# MST3K_Billboard.net
KiCad netlist of a schematic drawn in EAGLE
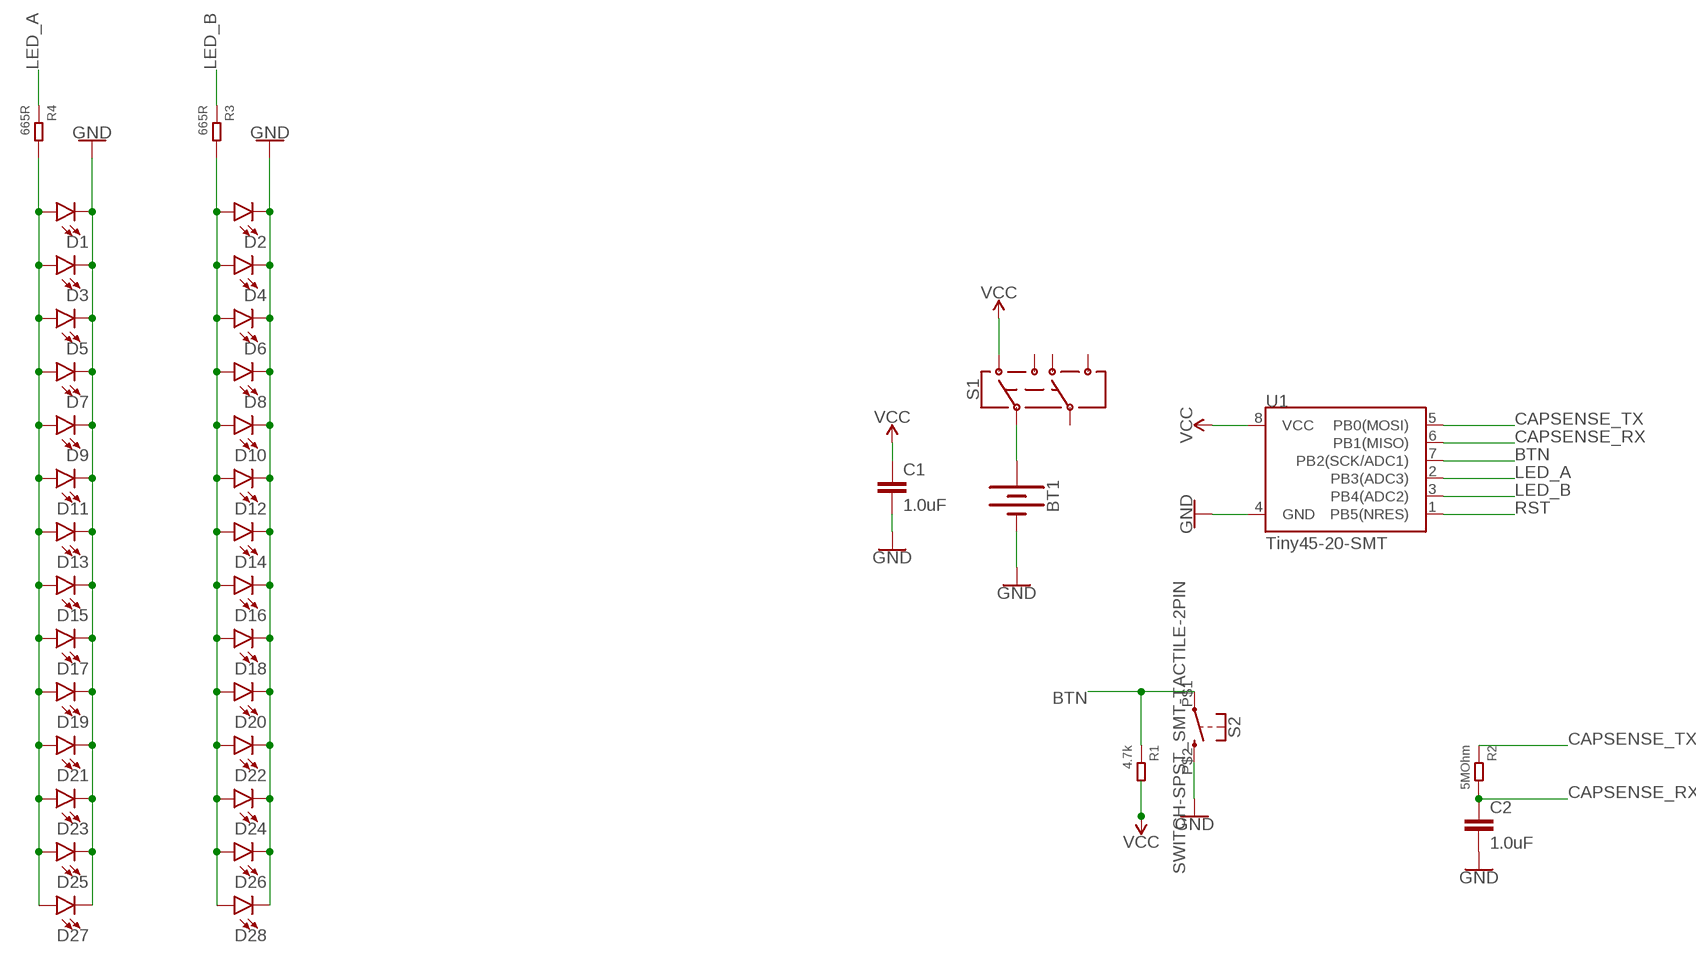
[diagram p0: schematic, sheet 1]

(export (version "E")
  (design (tool "Eeschema 10.0.6"))
  (components
    (comp (ref "BT1")
      (value "BATTERY-20MM_SMD_4LEGS")
      (footprint "eagle-import:BATTCON_20MM_4LEGS")
      (libsource (lib "eagle-import") (part "BATTERY-20MM_SMD_4LEGS"))
    )
    (comp (ref "C1")
      (value "1.0uF")
      (footprint "eagle-import:0805")
      (libsource (lib "eagle-import") (part "1.0UF-0805-25V-10%"))
    )
    (comp (ref "C2")
      (value "1.0uF")
      (footprint "eagle-import:0805")
      (libsource (lib "eagle-import") (part "1.0UF-0805-25V-10%"))
    )
    (comp (ref "D1")
      (value "LED-3MM-NO_SILK")
      (footprint "eagle-import:LED_3MM-NS")
      (libsource (lib "eagle-import") (part "LED-3MM-NO_SILK"))
    )
    (comp (ref "D2")
      (value "LED-3MM-NO_SILK")
      (footprint "eagle-import:LED_3MM-NS")
      (libsource (lib "eagle-import") (part "LED-3MM-NO_SILK"))
    )
    (comp (ref "D3")
      (value "LED-3MM-NO_SILK")
      (footprint "eagle-import:LED_3MM-NS")
      (libsource (lib "eagle-import") (part "LED-3MM-NO_SILK"))
    )
    (comp (ref "D4")
      (value "LED-3MM-NO_SILK")
      (footprint "eagle-import:LED_3MM-NS")
      (libsource (lib "eagle-import") (part "LED-3MM-NO_SILK"))
    )
    (comp (ref "D5")
      (value "LED-3MM-NO_SILK")
      (footprint "eagle-import:LED_3MM-NS")
      (libsource (lib "eagle-import") (part "LED-3MM-NO_SILK"))
    )
    (comp (ref "D6")
      (value "LED-3MM-NO_SILK")
      (footprint "eagle-import:LED_3MM-NS")
      (libsource (lib "eagle-import") (part "LED-3MM-NO_SILK"))
    )
    (comp (ref "D7")
      (value "LED-3MM-NO_SILK")
      (footprint "eagle-import:LED_3MM-NS")
      (libsource (lib "eagle-import") (part "LED-3MM-NO_SILK"))
    )
    (comp (ref "D8")
      (value "LED-3MM-NO_SILK")
      (footprint "eagle-import:LED_3MM-NS")
      (libsource (lib "eagle-import") (part "LED-3MM-NO_SILK"))
    )
    (comp (ref "D9")
      (value "LED-3MM-NO_SILK")
      (footprint "eagle-import:LED_3MM-NS")
      (libsource (lib "eagle-import") (part "LED-3MM-NO_SILK"))
    )
    (comp (ref "D10")
      (value "LED-3MM-NO_SILK")
      (footprint "eagle-import:LED_3MM-NS")
      (libsource (lib "eagle-import") (part "LED-3MM-NO_SILK"))
    )
    (comp (ref "D11")
      (value "LED-3MM-NO_SILK")
      (footprint "eagle-import:LED_3MM-NS")
      (libsource (lib "eagle-import") (part "LED-3MM-NO_SILK"))
    )
    (comp (ref "D12")
      (value "LED-3MM-NO_SILK")
      (footprint "eagle-import:LED_3MM-NS")
      (libsource (lib "eagle-import") (part "LED-3MM-NO_SILK"))
    )
    (comp (ref "D13")
      (value "LED-3MM-NO_SILK")
      (footprint "eagle-import:LED_3MM-NS")
      (libsource (lib "eagle-import") (part "LED-3MM-NO_SILK"))
    )
    (comp (ref "D14")
      (value "LED-3MM-NO_SILK")
      (footprint "eagle-import:LED_3MM-NS")
      (libsource (lib "eagle-import") (part "LED-3MM-NO_SILK"))
    )
    (comp (ref "D15")
      (value "LED-3MM-NO_SILK")
      (footprint "eagle-import:LED_3MM-NS")
      (libsource (lib "eagle-import") (part "LED-3MM-NO_SILK"))
    )
    (comp (ref "D16")
      (value "LED-3MM-NO_SILK")
      (footprint "eagle-import:LED_3MM-NS")
      (libsource (lib "eagle-import") (part "LED-3MM-NO_SILK"))
    )
    (comp (ref "D17")
      (value "LED-3MM-NO_SILK")
      (footprint "eagle-import:LED_3MM-NS")
      (libsource (lib "eagle-import") (part "LED-3MM-NO_SILK"))
    )
    (comp (ref "D18")
      (value "LED-3MM-NO_SILK")
      (footprint "eagle-import:LED_3MM-NS")
      (libsource (lib "eagle-import") (part "LED-3MM-NO_SILK"))
    )
    (comp (ref "D19")
      (value "LED-3MM-NO_SILK")
      (footprint "eagle-import:LED_3MM-NS")
      (libsource (lib "eagle-import") (part "LED-3MM-NO_SILK"))
    )
    (comp (ref "D20")
      (value "LED-3MM-NO_SILK")
      (footprint "eagle-import:LED_3MM-NS")
      (libsource (lib "eagle-import") (part "LED-3MM-NO_SILK"))
    )
    (comp (ref "D21")
      (value "LED-3MM-NO_SILK")
      (footprint "eagle-import:LED_3MM-NS")
      (libsource (lib "eagle-import") (part "LED-3MM-NO_SILK"))
    )
    (comp (ref "D22")
      (value "LED-3MM-NO_SILK")
      (footprint "eagle-import:LED_3MM-NS")
      (libsource (lib "eagle-import") (part "LED-3MM-NO_SILK"))
    )
    (comp (ref "D23")
      (value "LED-3MM-NO_SILK")
      (footprint "eagle-import:LED_3MM-NS")
      (libsource (lib "eagle-import") (part "LED-3MM-NO_SILK"))
    )
    (comp (ref "D24")
      (value "LED-3MM-NO_SILK")
      (footprint "eagle-import:LED_3MM-NS")
      (libsource (lib "eagle-import") (part "LED-3MM-NO_SILK"))
    )
    (comp (ref "D25")
      (value "LED-3MM-NO_SILK")
      (footprint "eagle-import:LED_3MM-NS")
      (libsource (lib "eagle-import") (part "LED-3MM-NO_SILK"))
    )
    (comp (ref "D26")
      (value "LED-3MM-NO_SILK")
      (footprint "eagle-import:LED_3MM-NS")
      (libsource (lib "eagle-import") (part "LED-3MM-NO_SILK"))
    )
    (comp (ref "D27")
      (value "LED-3MM-NO_SILK")
      (footprint "eagle-import:LED_3MM-NS")
      (libsource (lib "eagle-import") (part "LED-3MM-NO_SILK"))
    )
    (comp (ref "D28")
      (value "LED-3MM-NO_SILK")
      (footprint "eagle-import:LED_3MM-NS")
      (libsource (lib "eagle-import") (part "LED-3MM-NO_SILK"))
    )
    (comp (ref "R1")
      (value "4.7k")
      (footprint "eagle-import:R0805")
      (fields (field (name "MPN") "RC0805JR-0747RL"))
      (libsource (lib "eagle-import") (part "SMD-RES-47R-5%-1/8W(0805)"))
    )
    (comp (ref "R2")
      (value "5MOhm")
      (footprint "eagle-import:R0805")
      (fields (field (name "MPN") "RC0805JR-0747RL"))
      (libsource (lib "eagle-import") (part "SMD-RES-47R-5%-1/8W(0805)"))
    )
    (comp (ref "R3")
      (value "665R")
      (footprint "eagle-import:R0805")
      (fields (field (name "MPN") "RC0805JR-0747RL"))
      (libsource (lib "eagle-import") (part "SMD-RES-47R-5%-1/8W(0805)"))
    )
    (comp (ref "R4")
      (value "665R")
      (footprint "eagle-import:R0805")
      (fields (field (name "MPN") "RC0805JR-0747RL"))
      (libsource (lib "eagle-import") (part "SMD-RES-47R-5%-1/8W(0805)"))
    )
    (comp (ref "S1")
      (value "SWITCH-DPDT-JS202011JCQN")
      (footprint "eagle-import:SWITCH_DPDT_SMD_JS202011JCQN")
      (libsource (lib "eagle-import") (part "SWITCH-DPDT-JS202011JCQN"))
    )
    (comp (ref "S2")
      (value "SWITCH-SPST_SMT-TACTILE-2PIN")
      (footprint "eagle-import:SMT_TACTILE_SWITCH_3X2MM")
      (libsource (lib "eagle-import") (part "SWITCH-SPST_SMT-TACTILE-2PIN"))
    )
    (comp (ref "U1")
      (value "Tiny45-20-SMT")
      (footprint "eagle-import:SO08-EIAJ_MCU")
      (libsource (lib "eagle-import") (part "ATTINY45TINY45-20-SMT"))
    )
  )
  (nets
    (net (code "1") (name "/BTN") (class "Default")
      (node (ref "R1") (pin "1") (pinfunction "1_1") (pintype "passive"))
      (node (ref "S2") (pin "P$1") (pinfunction "1_P$1") (pintype "passive"))
      (node (ref "U1") (pin "7") (pinfunction "PB2(SCK/ADC1)_7") (pintype "bidirectional"))
    )
    (net (code "2") (name "/CAPSENSE_RX") (class "Default")
      (node (ref "C2") (pin "1") (pinfunction "1_1") (pintype "passive"))
      (node (ref "R2") (pin "2") (pinfunction "2_2") (pintype "passive"))
      (node (ref "U1") (pin "6") (pinfunction "PB1(MISO)_6") (pintype "bidirectional"))
    )
    (net (code "3") (name "/CAPSENSE_TX") (class "Default")
      (node (ref "R2") (pin "1") (pinfunction "1_1") (pintype "passive"))
      (node (ref "U1") (pin "5") (pinfunction "PB0(MOSI)_5") (pintype "bidirectional"))
    )
    (net (code "4") (name "/LED_A") (class "Default")
      (node (ref "R4") (pin "1") (pinfunction "1_1") (pintype "passive"))
      (node (ref "U1") (pin "2") (pinfunction "PB3(ADC3)_2") (pintype "bidirectional"))
    )
    (net (code "5") (name "/LED_B") (class "Default")
      (node (ref "R3") (pin "1") (pinfunction "1_1") (pintype "passive"))
      (node (ref "U1") (pin "3") (pinfunction "PB4(ADC2)_3") (pintype "bidirectional"))
    )
    (net (code "6") (name "/RST") (class "Default")
      (node (ref "U1") (pin "1") (pinfunction "PB5(NRES)_1") (pintype "bidirectional"))
    )
    (net (code "7") (name "GND") (class "Default")
      (node (ref "BT1") (pin "NEGATIVE") (pinfunction "-_NEGATIVE") (pintype "power_in"))
      (node (ref "C1") (pin "2") (pinfunction "2_2") (pintype "passive"))
      (node (ref "C2") (pin "2") (pinfunction "2_2") (pintype "passive"))
      (node (ref "D1") (pin "K") (pinfunction "C_K") (pintype "passive"))
      (node (ref "D10") (pin "K") (pinfunction "C_K") (pintype "passive"))
      (node (ref "D11") (pin "K") (pinfunction "C_K") (pintype "passive"))
      (node (ref "D12") (pin "K") (pinfunction "C_K") (pintype "passive"))
      (node (ref "D13") (pin "K") (pinfunction "C_K") (pintype "passive"))
      (node (ref "D14") (pin "K") (pinfunction "C_K") (pintype "passive"))
      (node (ref "D15") (pin "K") (pinfunction "C_K") (pintype "passive"))
      (node (ref "D16") (pin "K") (pinfunction "C_K") (pintype "passive"))
      (node (ref "D17") (pin "K") (pinfunction "C_K") (pintype "passive"))
      (node (ref "D18") (pin "K") (pinfunction "C_K") (pintype "passive"))
      (node (ref "D19") (pin "K") (pinfunction "C_K") (pintype "passive"))
      (node (ref "D2") (pin "K") (pinfunction "C_K") (pintype "passive"))
      (node (ref "D20") (pin "K") (pinfunction "C_K") (pintype "passive"))
      (node (ref "D21") (pin "K") (pinfunction "C_K") (pintype "passive"))
      (node (ref "D22") (pin "K") (pinfunction "C_K") (pintype "passive"))
      (node (ref "D23") (pin "K") (pinfunction "C_K") (pintype "passive"))
      (node (ref "D24") (pin "K") (pinfunction "C_K") (pintype "passive"))
      (node (ref "D25") (pin "K") (pinfunction "C_K") (pintype "passive"))
      (node (ref "D26") (pin "K") (pinfunction "C_K") (pintype "passive"))
      (node (ref "D27") (pin "K") (pinfunction "C_K") (pintype "passive"))
      (node (ref "D28") (pin "K") (pinfunction "C_K") (pintype "passive"))
      (node (ref "D3") (pin "K") (pinfunction "C_K") (pintype "passive"))
      (node (ref "D4") (pin "K") (pinfunction "C_K") (pintype "passive"))
      (node (ref "D5") (pin "K") (pinfunction "C_K") (pintype "passive"))
      (node (ref "D6") (pin "K") (pinfunction "C_K") (pintype "passive"))
      (node (ref "D7") (pin "K") (pinfunction "C_K") (pintype "passive"))
      (node (ref "D8") (pin "K") (pinfunction "C_K") (pintype "passive"))
      (node (ref "D9") (pin "K") (pinfunction "C_K") (pintype "passive"))
      (node (ref "S2") (pin "P$2") (pinfunction "2_P$2") (pintype "passive"))
      (node (ref "U1") (pin "4") (pinfunction "GND_4") (pintype "bidirectional"))
    )
    (net (code "8") (name "Net-(D1-PadA)") (class "Default")
      (node (ref "D1") (pin "A") (pinfunction "A_A") (pintype "passive"))
      (node (ref "D11") (pin "A") (pinfunction "A_A") (pintype "passive"))
      (node (ref "D13") (pin "A") (pinfunction "A_A") (pintype "passive"))
      (node (ref "D15") (pin "A") (pinfunction "A_A") (pintype "passive"))
      (node (ref "D17") (pin "A") (pinfunction "A_A") (pintype "passive"))
      (node (ref "D19") (pin "A") (pinfunction "A_A") (pintype "passive"))
      (node (ref "D21") (pin "A") (pinfunction "A_A") (pintype "passive"))
      (node (ref "D23") (pin "A") (pinfunction "A_A") (pintype "passive"))
      (node (ref "D25") (pin "A") (pinfunction "A_A") (pintype "passive"))
      (node (ref "D27") (pin "A") (pinfunction "A_A") (pintype "passive"))
      (node (ref "D3") (pin "A") (pinfunction "A_A") (pintype "passive"))
      (node (ref "D5") (pin "A") (pinfunction "A_A") (pintype "passive"))
      (node (ref "D7") (pin "A") (pinfunction "A_A") (pintype "passive"))
      (node (ref "D9") (pin "A") (pinfunction "A_A") (pintype "passive"))
      (node (ref "R4") (pin "2") (pinfunction "2_2") (pintype "passive"))
    )
    (net (code "9") (name "Net-(D10-PadA)") (class "Default")
      (node (ref "D10") (pin "A") (pinfunction "A_A") (pintype "passive"))
      (node (ref "D12") (pin "A") (pinfunction "A_A") (pintype "passive"))
      (node (ref "D14") (pin "A") (pinfunction "A_A") (pintype "passive"))
      (node (ref "D16") (pin "A") (pinfunction "A_A") (pintype "passive"))
      (node (ref "D18") (pin "A") (pinfunction "A_A") (pintype "passive"))
      (node (ref "D2") (pin "A") (pinfunction "A_A") (pintype "passive"))
      (node (ref "D20") (pin "A") (pinfunction "A_A") (pintype "passive"))
      (node (ref "D22") (pin "A") (pinfunction "A_A") (pintype "passive"))
      (node (ref "D24") (pin "A") (pinfunction "A_A") (pintype "passive"))
      (node (ref "D26") (pin "A") (pinfunction "A_A") (pintype "passive"))
      (node (ref "D28") (pin "A") (pinfunction "A_A") (pintype "passive"))
      (node (ref "D4") (pin "A") (pinfunction "A_A") (pintype "passive"))
      (node (ref "D6") (pin "A") (pinfunction "A_A") (pintype "passive"))
      (node (ref "D8") (pin "A") (pinfunction "A_A") (pintype "passive"))
      (node (ref "R3") (pin "2") (pinfunction "2_2") (pintype "passive"))
    )
    (net (code "10") (name "Net-(S1-2)") (class "Default")
      (node (ref "BT1") (pin "POSITIVE@1") (pinfunction "+_POSITIVE@1") (pintype "power_in"))
      (node (ref "BT1") (pin "POSITIVE@2") (pinfunction "+_POSITIVE@2") (pintype "power_in"))
      (node (ref "BT1") (pin "POSITIVE@3") (pinfunction "+_POSITIVE@3") (pintype "power_in"))
      (node (ref "BT1") (pin "POSITIVE@4") (pinfunction "+_POSITIVE@4") (pintype "power_in"))
      (node (ref "S1") (pin "P$2") (pinfunction "2_P$2") (pintype "bidirectional"))
    )
    (net (code "11") (name "VCC") (class "Default")
      (node (ref "C1") (pin "1") (pinfunction "1_1") (pintype "passive"))
      (node (ref "R1") (pin "2") (pinfunction "2_2") (pintype "passive"))
      (node (ref "S1") (pin "P$1") (pinfunction "1_P$1") (pintype "bidirectional"))
      (node (ref "U1") (pin "8") (pinfunction "VCC_8") (pintype "bidirectional"))
    )
    (net (code "12") (name "unconnected-(S1-3-PadP$3)") (class "Default")
      (node (ref "S1") (pin "P$3") (pinfunction "3_P$3") (pintype "bidirectional"))
    )
    (net (code "13") (name "unconnected-(S1-4-PadP$4)") (class "Default")
      (node (ref "S1") (pin "P$4") (pinfunction "4_P$4") (pintype "bidirectional"))
    )
    (net (code "14") (name "unconnected-(S1-5-PadP$5)") (class "Default")
      (node (ref "S1") (pin "P$5") (pinfunction "5_P$5") (pintype "bidirectional"))
    )
    (net (code "15") (name "unconnected-(S1-6-PadP$6)") (class "Default")
      (node (ref "S1") (pin "P$6") (pinfunction "6_P$6") (pintype "bidirectional"))
    )
  )
)
